# ap-pam-v2.net
KiCad netlist of a schematic drawn in Altium Designer
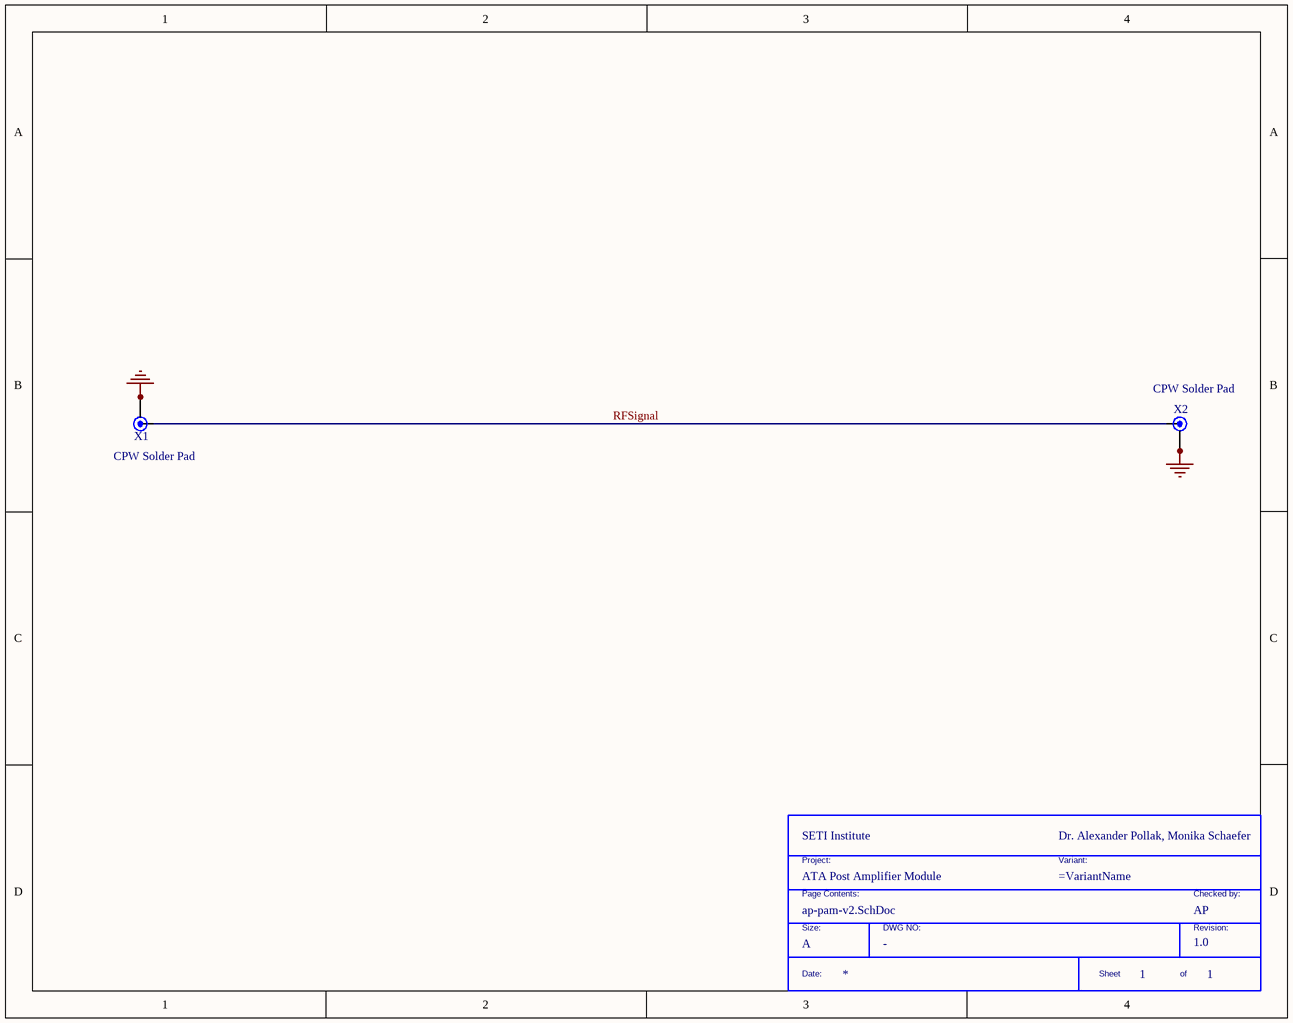
[diagram p0: ap-pam-v2.SchDoc]

(export (version "E")
  (design (tool "Eeschema 10.0.6"))
  (components
    (comp (ref "*")
      (value "~")
      (description "Standard Title Block")
      (fields (field (name "DWG NO") "-") (field (name "SIZE") "A") (field (name "CHECKED BY") "AP"))
      (libsource (lib "ap-pam") (part "TitleBlock"))
    )
    (comp (ref "X1")
      (value "CPW Solder Pad")
      (footprint "CPW Edge Connector")
      (description "Solder pad for RF Coplanar Waveguide Rogers 4350B Thickness 0.020\" Copper 1oz")
      (libsource (lib "ap-pam") (part "RF  CPW Solder Pad"))
    )
    (comp (ref "X2")
      (value "CPW Solder Pad")
      (footprint "CPW Edge Connector")
      (description "Solder pad for RF Coplanar Waveguide Rogers 4350B Thickness 0.020\" Copper 1oz")
      (libsource (lib "ap-pam") (part "RF  CPW Solder Pad"))
    )
  )
  (nets
    (net (code "1") (name "/RFSignal") (class "Default")
      (node (ref "X1") (pin "1") (pinfunction "1_1") (pintype "passive"))
      (node (ref "X2") (pin "1") (pinfunction "1_1") (pintype "passive"))
    )
    (net (code "2") (name "GND") (class "Default")
      (node (ref "X1") (pin "2") (pinfunction "2_2") (pintype "passive"))
      (node (ref "X1") (pin "3") (pinfunction "3_3") (pintype "passive"))
      (node (ref "X2") (pin "2") (pinfunction "2_2") (pintype "passive"))
      (node (ref "X2") (pin "3") (pinfunction "3_3") (pintype "passive"))
    )
  )
)
